# Thruster_Ctl.net
KiCad netlist of a schematic drawn in EAGLE
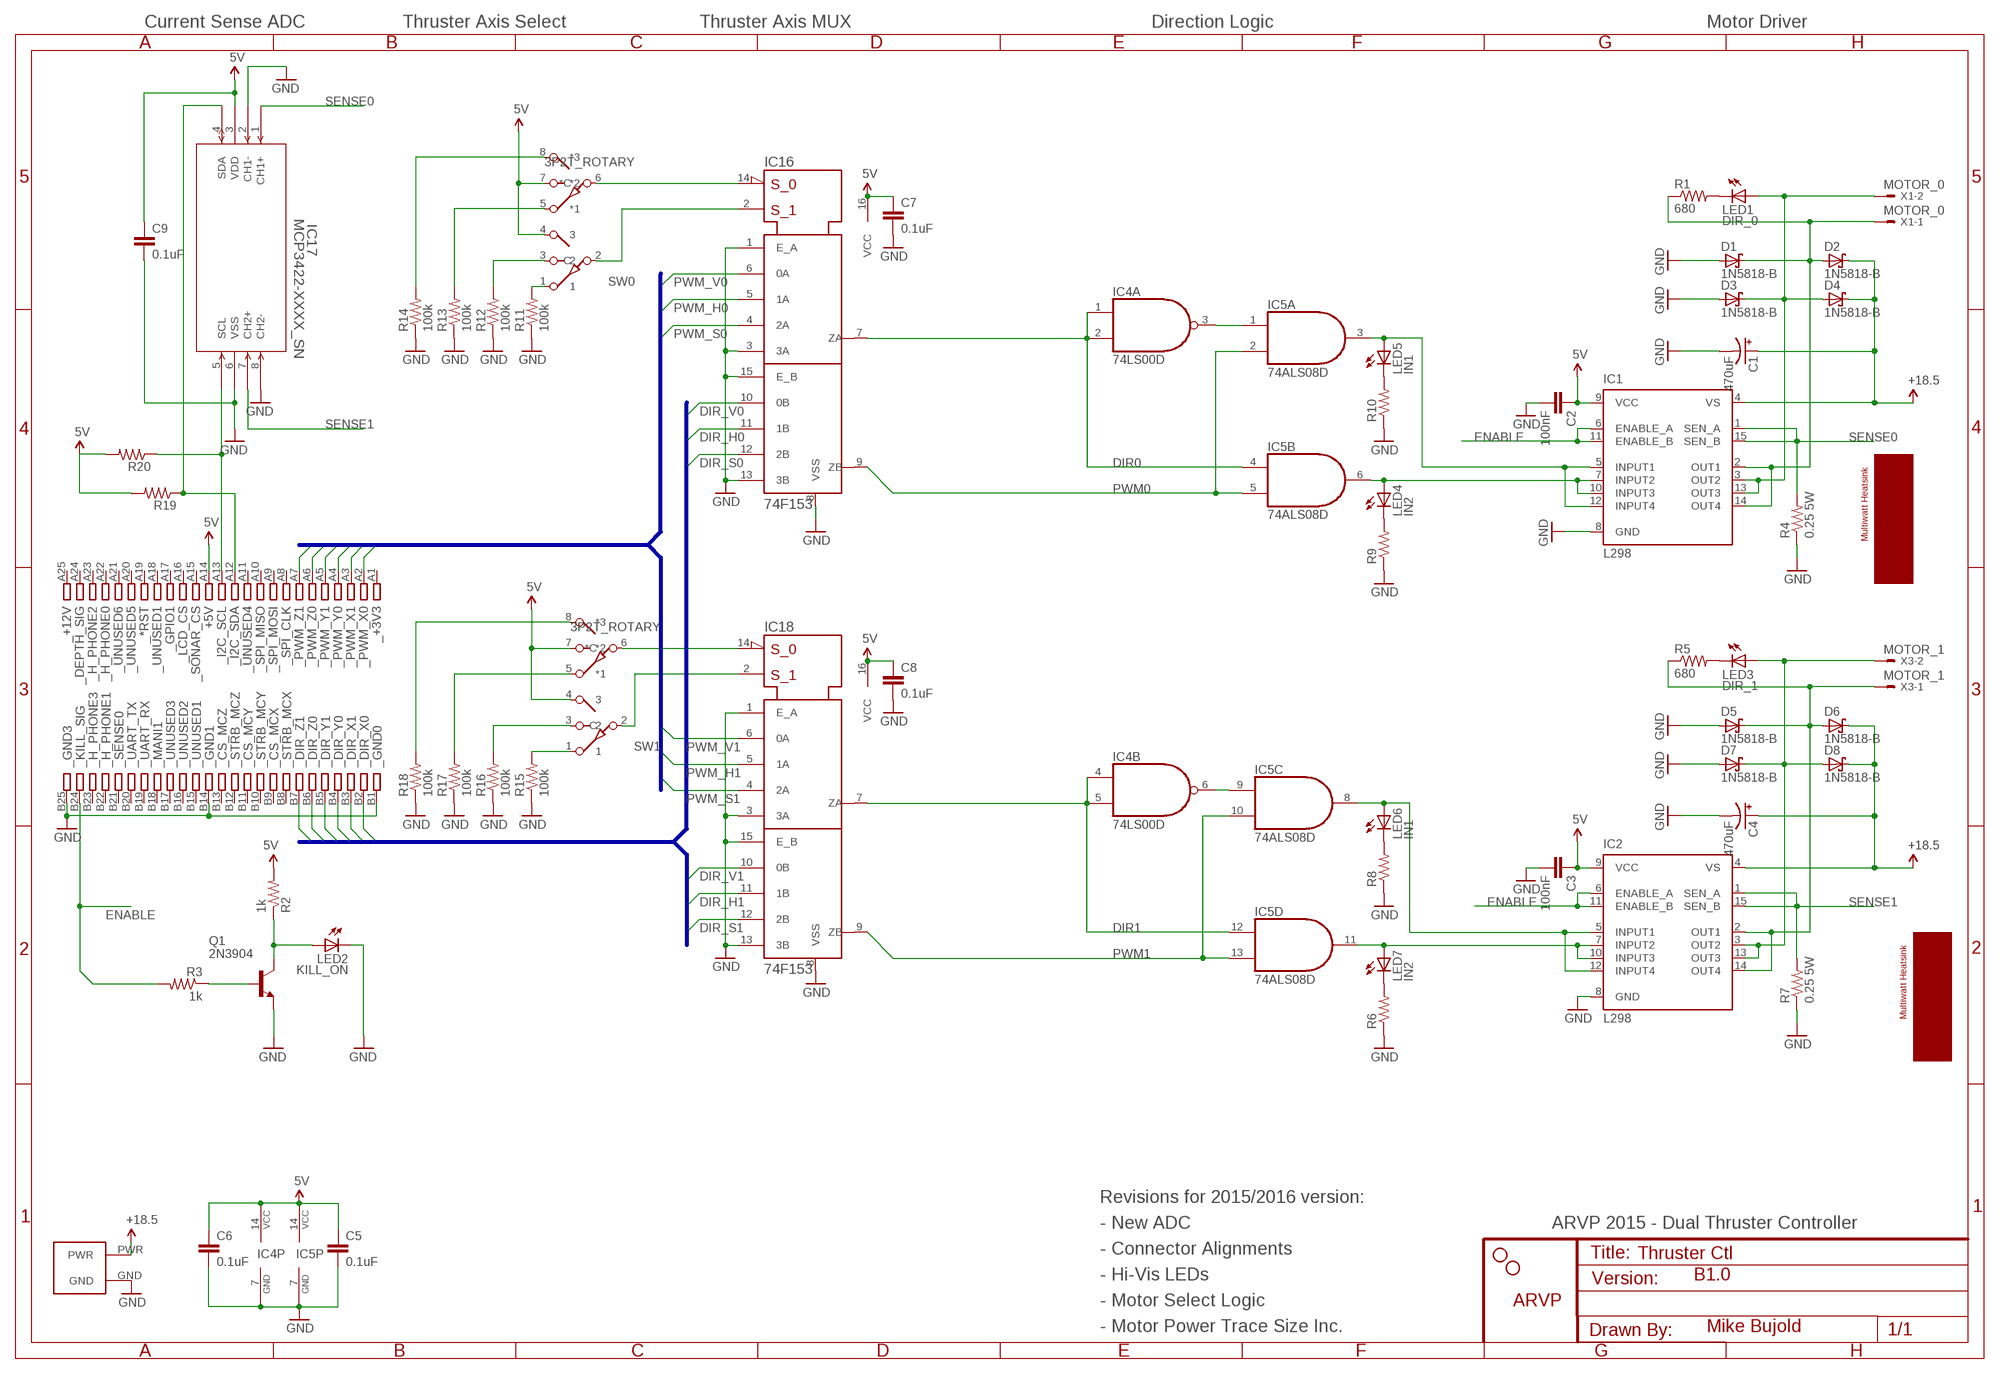
[diagram p0: schematic, sheet 1]

(export (version "E")
  (design (tool "Eeschema 10.0.6"))
  (components
    (comp (ref "C1")
      (value "470uF")
      (footprint "eagle-import:E25-10")
      (libsource (lib "eagle-import") (part "CPOL-USE25-10AXIAL"))
    )
    (comp (ref "C2")
      (value "100nF")
      (footprint "eagle-import:CAP-PTH-SMALL")
      (libsource (lib "eagle-import") (part "CAPPTH"))
    )
    (comp (ref "C3")
      (value "100nF")
      (footprint "eagle-import:CAP-PTH-SMALL")
      (libsource (lib "eagle-import") (part "CAPPTH"))
    )
    (comp (ref "C4")
      (value "470uF")
      (footprint "eagle-import:E25-10")
      (libsource (lib "eagle-import") (part "CPOL-USE25-10AXIAL"))
    )
    (comp (ref "C5")
      (value "0.1uF")
      (footprint "eagle-import:1206")
      (libsource (lib "eagle-import") (part "SparkFun-Capacitors_CAP1206"))
    )
    (comp (ref "C6")
      (value "0.1uF")
      (footprint "eagle-import:1206")
      (libsource (lib "eagle-import") (part "SparkFun-Capacitors_CAP1206"))
    )
    (comp (ref "C7")
      (value "0.1uF")
      (footprint "eagle-import:1206")
      (libsource (lib "eagle-import") (part "SparkFun-Capacitors_CAP1206"))
    )
    (comp (ref "C8")
      (value "0.1uF")
      (footprint "eagle-import:1206")
      (libsource (lib "eagle-import") (part "SparkFun-Capacitors_CAP1206"))
    )
    (comp (ref "C9")
      (value "0.1uF")
      (footprint "eagle-import:1206")
      (libsource (lib "eagle-import") (part "SparkFun-Capacitors_CAP1206"))
    )
    (comp (ref "D1")
      (value "1N5818-B")
      (footprint "eagle-import:DO41-7.6")
      (libsource (lib "eagle-import") (part "1N5818-B"))
    )
    (comp (ref "D2")
      (value "1N5818-B")
      (footprint "eagle-import:DO41-7.6")
      (libsource (lib "eagle-import") (part "1N5818-B"))
    )
    (comp (ref "D3")
      (value "1N5818-B")
      (footprint "eagle-import:DO41-7.6")
      (libsource (lib "eagle-import") (part "1N5818-B"))
    )
    (comp (ref "D4")
      (value "1N5818-B")
      (footprint "eagle-import:DO41-7.6")
      (libsource (lib "eagle-import") (part "1N5818-B"))
    )
    (comp (ref "D5")
      (value "1N5818-B")
      (footprint "eagle-import:DO41-7.6")
      (libsource (lib "eagle-import") (part "1N5818-B"))
    )
    (comp (ref "D6")
      (value "1N5818-B")
      (footprint "eagle-import:DO41-7.6")
      (libsource (lib "eagle-import") (part "1N5818-B"))
    )
    (comp (ref "D7")
      (value "1N5818-B")
      (footprint "eagle-import:DO41-7.6")
      (libsource (lib "eagle-import") (part "1N5818-B"))
    )
    (comp (ref "D8")
      (value "1N5818-B")
      (footprint "eagle-import:DO41-7.6")
      (libsource (lib "eagle-import") (part "1N5818-B"))
    )
    (comp (ref "IC1")
      (value "L298")
      (footprint "eagle-import:MULTIWATT-15")
      (fields (field (name "MPN") "L298N"))
      (libsource (lib "eagle-import") (part "L298"))
    )
    (comp (ref "IC2")
      (value "L298")
      (footprint "eagle-import:MULTIWATT-15")
      (fields (field (name "MPN") "L298N"))
      (libsource (lib "eagle-import") (part "L298"))
    )
    (comp (ref "IC4")
      (value "74LS00D")
      (footprint "eagle-import:SO14")
      (libsource (lib "eagle-import") (part "7400DLS"))
    )
    (comp (ref "IC5")
      (value "74ALS08D")
      (footprint "eagle-import:SO14")
      (libsource (lib "eagle-import") (part "7408DALS"))
    )
    (comp (ref "IC16")
      (value "74F153")
      (footprint "eagle-import:SO16")
      (libsource (lib "eagle-import") (part "74F153"))
    )
    (comp (ref "IC17")
      (value "MCP3422-XXXX_SN")
      (footprint "eagle-import:SOIC8-N_MC")
      (libsource (lib "eagle-import") (part "MCP3422-XXXX_SN"))
    )
    (comp (ref "IC18")
      (value "74F153")
      (footprint "eagle-import:SO16")
      (libsource (lib "eagle-import") (part "74F153"))
    )
    (comp (ref "JP1")
      (value "STAND-OFF")
      (footprint "eagle-import:STAND-OFF")
      (libsource (lib "eagle-import") (part "STAND-OFF"))
    )
    (comp (ref "JP4")
      (value "STAND-OFF")
      (footprint "eagle-import:STAND-OFF")
      (libsource (lib "eagle-import") (part "STAND-OFF"))
    )
    (comp (ref "LED1")
      (value "DIR_0")
      (footprint "eagle-import:LED5MM")
      (libsource (lib "eagle-import") (part "led_LED5MM"))
    )
    (comp (ref "LED2")
      (value "KILL_ON")
      (footprint "eagle-import:LED5MM")
      (libsource (lib "eagle-import") (part "led_LED5MM"))
    )
    (comp (ref "LED3")
      (value "DIR_1")
      (footprint "eagle-import:LED5MM")
      (libsource (lib "eagle-import") (part "led_LED5MM"))
    )
    (comp (ref "LED4")
      (value "IN2")
      (footprint "eagle-import:1206")
      (libsource (lib "eagle-import") (part "LEDSMT1206"))
    )
    (comp (ref "LED5")
      (value "IN1")
      (footprint "eagle-import:1206")
      (libsource (lib "eagle-import") (part "LEDSMT1206"))
    )
    (comp (ref "LED6")
      (value "IN1")
      (footprint "eagle-import:1206")
      (libsource (lib "eagle-import") (part "LEDSMT1206"))
    )
    (comp (ref "LED7")
      (value "IN2")
      (footprint "eagle-import:1206")
      (libsource (lib "eagle-import") (part "LEDSMT1206"))
    )
    (comp (ref "Q1")
      (value "2N3904")
      (footprint "eagle-import:TO92")
      (libsource (lib "eagle-import") (part "2N3904"))
    )
    (comp (ref "R1")
      (value "680")
      (footprint "eagle-import:AXIAL-0.4")
      (libsource (lib "eagle-import") (part "RESISTORPTH-1/4W"))
    )
    (comp (ref "R2")
      (value "1k")
      (footprint "eagle-import:AXIAL-0.4")
      (libsource (lib "eagle-import") (part "RESISTORPTH-1/4W"))
    )
    (comp (ref "R3")
      (value "1k")
      (footprint "eagle-import:AXIAL-0.4")
      (libsource (lib "eagle-import") (part "RESISTORPTH-1/4W"))
    )
    (comp (ref "R4")
      (value "0.25 5W")
      (footprint "eagle-import:0922_22")
      (libsource (lib "eagle-import") (part "RESISTOR"))
    )
    (comp (ref "R5")
      (value "680")
      (footprint "eagle-import:AXIAL-0.4")
      (libsource (lib "eagle-import") (part "RESISTORPTH-1/4W"))
    )
    (comp (ref "R6")
      (value "RESISTOR1206")
      (footprint "eagle-import:1206")
      (libsource (lib "eagle-import") (part "SparkFun-Passives_RESISTOR1206"))
    )
    (comp (ref "R7")
      (value "0.25 5W")
      (footprint "eagle-import:0922_22")
      (libsource (lib "eagle-import") (part "RESISTOR"))
    )
    (comp (ref "R8")
      (value "RESISTOR1206")
      (footprint "eagle-import:1206")
      (libsource (lib "eagle-import") (part "SparkFun-Passives_RESISTOR1206"))
    )
    (comp (ref "R9")
      (value "RESISTOR1206")
      (footprint "eagle-import:1206")
      (libsource (lib "eagle-import") (part "SparkFun-Passives_RESISTOR1206"))
    )
    (comp (ref "R10")
      (value "RESISTOR1206")
      (footprint "eagle-import:1206")
      (libsource (lib "eagle-import") (part "SparkFun-Passives_RESISTOR1206"))
    )
    (comp (ref "R11")
      (value "100k")
      (footprint "eagle-import:1206")
      (libsource (lib "eagle-import") (part "SparkFun-Passives_RESISTOR1206"))
    )
    (comp (ref "R12")
      (value "100k")
      (footprint "eagle-import:1206")
      (libsource (lib "eagle-import") (part "SparkFun-Passives_RESISTOR1206"))
    )
    (comp (ref "R13")
      (value "100k")
      (footprint "eagle-import:1206")
      (libsource (lib "eagle-import") (part "SparkFun-Passives_RESISTOR1206"))
    )
    (comp (ref "R14")
      (value "100k")
      (footprint "eagle-import:1206")
      (libsource (lib "eagle-import") (part "SparkFun-Passives_RESISTOR1206"))
    )
    (comp (ref "R15")
      (value "100k")
      (footprint "eagle-import:1206")
      (libsource (lib "eagle-import") (part "SparkFun-Passives_RESISTOR1206"))
    )
    (comp (ref "R16")
      (value "100k")
      (footprint "eagle-import:1206")
      (libsource (lib "eagle-import") (part "SparkFun-Passives_RESISTOR1206"))
    )
    (comp (ref "R17")
      (value "100k")
      (footprint "eagle-import:1206")
      (libsource (lib "eagle-import") (part "SparkFun-Passives_RESISTOR1206"))
    )
    (comp (ref "R18")
      (value "100k")
      (footprint "eagle-import:1206")
      (libsource (lib "eagle-import") (part "SparkFun-Passives_RESISTOR1206"))
    )
    (comp (ref "R19")
      (value "RESISTOR1206")
      (footprint "eagle-import:1206")
      (libsource (lib "eagle-import") (part "SparkFun-Passives_RESISTOR1206"))
    )
    (comp (ref "R20")
      (value "RESISTOR1206")
      (footprint "eagle-import:1206")
      (libsource (lib "eagle-import") (part "SparkFun-Passives_RESISTOR1206"))
    )
    (comp (ref "SW0")
      (value "3P2T_ROTARY")
      (footprint "eagle-import:DIL08")
      (libsource (lib "eagle-import") (part "3P2T_ROTARY"))
    )
    (comp (ref "SW1")
      (value "3P2T_ROTARY")
      (footprint "eagle-import:DIL08")
      (libsource (lib "eagle-import") (part "3P2T_ROTARY"))
    )
    (comp (ref "U$4")
      (value "ARVP_LOGO")
      (footprint "eagle-import:ARVP")
      (libsource (lib "eagle-import") (part "ARVP_LOGO"))
    )
    (comp (ref "U$7")
      (value "AND_PWR")
      (footprint "eagle-import:AND_PWR")
      (libsource (lib "eagle-import") (part "AND_PWR"))
    )
    (comp (ref "U$9")
      (value "L298_HS")
      (footprint "eagle-import:HEATSINK_MW")
      (libsource (lib "eagle-import") (part "L298_HS"))
    )
    (comp (ref "U$10")
      (value "L298_HS")
      (footprint "eagle-import:HEATSINK_MW")
      (libsource (lib "eagle-import") (part "L298_HS"))
    )
    (comp (ref "U$19")
      (value "CARD_50PIN")
      (footprint "eagle-import:CARD_50PIN")
      (libsource (lib "eagle-import") (part "CARD_50PIN"))
    )
    (comp (ref "X1")
      (value "MOTOR_0")
      (footprint "eagle-import:KK-156-2")
      (libsource (lib "eagle-import") (part "KK-156-2"))
    )
    (comp (ref "X3")
      (value "MOTOR_1")
      (footprint "eagle-import:KK-156-2")
      (libsource (lib "eagle-import") (part "KK-156-2"))
    )
  )
  (nets
    (net (code "1") (name "+18.5") (class "Default")
      (node (ref "C1") (pin "+") (pinfunction "+_+") (pintype "passive"))
      (node (ref "C4") (pin "+") (pinfunction "+_+") (pintype "passive"))
      (node (ref "D2") (pin "C") (pinfunction "C_C") (pintype "passive"))
      (node (ref "D4") (pin "C") (pinfunction "C_C") (pintype "passive"))
      (node (ref "D6") (pin "C") (pinfunction "C_C") (pintype "passive"))
      (node (ref "D8") (pin "C") (pinfunction "C_C") (pintype "passive"))
      (node (ref "IC1") (pin "4") (pinfunction "VS_4") (pintype "power_in"))
      (node (ref "IC2") (pin "4") (pinfunction "VS_4") (pintype "power_in"))
      (node (ref "U$7") (pin "PWR") (pinfunction "PWR_PWR") (pintype "bidirectional"))
    )
    (net (code "2") (name "/DIR0") (class "Default")
      (node (ref "IC16") (pin "7") (pinfunction "ZA_7") (pintype "output"))
      (node (ref "IC4") (pin "1") (pinfunction "I0_1") (pintype "input"))
      (node (ref "IC4") (pin "2") (pinfunction "I1_2") (pintype "input"))
      (node (ref "IC5") (pin "4") (pinfunction "I0_4") (pintype "input"))
    )
    (net (code "3") (name "/DIR1") (class "Default")
      (node (ref "IC18") (pin "7") (pinfunction "ZA_7") (pintype "output"))
      (node (ref "IC4") (pin "4") (pinfunction "I0_4") (pintype "input"))
      (node (ref "IC4") (pin "5") (pinfunction "I1_5") (pintype "input"))
      (node (ref "IC5") (pin "12") (pinfunction "I0_12") (pintype "input"))
    )
    (net (code "4") (name "/DIR_H0") (class "Default")
      (node (ref "IC16") (pin "11") (pinfunction "1B_11") (pintype "input"))
      (node (ref "U$19") (pin "B4") (pinfunction "B4_B4") (pintype "bidirectional"))
    )
    (net (code "5") (name "/DIR_H1") (class "Default")
      (node (ref "IC18") (pin "11") (pinfunction "1B_11") (pintype "input"))
      (node (ref "U$19") (pin "B5") (pinfunction "B5_B5") (pintype "bidirectional"))
    )
    (net (code "6") (name "/DIR_S0") (class "Default")
      (node (ref "IC16") (pin "12") (pinfunction "2B_12") (pintype "input"))
      (node (ref "U$19") (pin "B6") (pinfunction "B6_B6") (pintype "bidirectional"))
    )
    (net (code "7") (name "/DIR_S1") (class "Default")
      (node (ref "IC18") (pin "12") (pinfunction "2B_12") (pintype "input"))
      (node (ref "U$19") (pin "B7") (pinfunction "B7_B7") (pintype "bidirectional"))
    )
    (net (code "8") (name "/DIR_V0") (class "Default")
      (node (ref "IC16") (pin "10") (pinfunction "0B_10") (pintype "input"))
      (node (ref "U$19") (pin "B2") (pinfunction "B2_B2") (pintype "bidirectional"))
    )
    (net (code "9") (name "/DIR_V1") (class "Default")
      (node (ref "IC18") (pin "10") (pinfunction "0B_10") (pintype "input"))
      (node (ref "U$19") (pin "B3") (pinfunction "B3_B3") (pintype "bidirectional"))
    )
    (net (code "10") (name "/ENABLE") (class "Default")
      (node (ref "IC1") (pin "11") (pinfunction "ENABLE_B_11") (pintype "input"))
      (node (ref "IC1") (pin "6") (pinfunction "ENABLE_A_6") (pintype "input"))
      (node (ref "IC2") (pin "11") (pinfunction "ENABLE_B_11") (pintype "input"))
      (node (ref "IC2") (pin "6") (pinfunction "ENABLE_A_6") (pintype "input"))
      (node (ref "R3") (pin "P$2") (pinfunction "2_P$2") (pintype "passive"))
      (node (ref "U$19") (pin "B24") (pinfunction "B24_B24") (pintype "bidirectional"))
    )
    (net (code "11") (name "/PWM0") (class "Default")
      (node (ref "IC16") (pin "9") (pinfunction "ZB_9") (pintype "output"))
      (node (ref "IC5") (pin "2") (pinfunction "I1_2") (pintype "input"))
      (node (ref "IC5") (pin "5") (pinfunction "I1_5") (pintype "input"))
    )
    (net (code "12") (name "/PWM1") (class "Default")
      (node (ref "IC18") (pin "9") (pinfunction "ZB_9") (pintype "output"))
      (node (ref "IC5") (pin "10") (pinfunction "I1_10") (pintype "input"))
      (node (ref "IC5") (pin "13") (pinfunction "I1_13") (pintype "input"))
    )
    (net (code "13") (name "/PWM_H0") (class "Default")
      (node (ref "IC16") (pin "5") (pinfunction "1A_5") (pintype "input"))
      (node (ref "U$19") (pin "A4") (pinfunction "A4_A4") (pintype "bidirectional"))
    )
    (net (code "14") (name "/PWM_H1") (class "Default")
      (node (ref "IC18") (pin "5") (pinfunction "1A_5") (pintype "input"))
      (node (ref "U$19") (pin "A5") (pinfunction "A5_A5") (pintype "bidirectional"))
    )
    (net (code "15") (name "/PWM_S0") (class "Default")
      (node (ref "IC16") (pin "4") (pinfunction "2A_4") (pintype "input"))
      (node (ref "U$19") (pin "A6") (pinfunction "A6_A6") (pintype "bidirectional"))
    )
    (net (code "16") (name "/PWM_S1") (class "Default")
      (node (ref "IC18") (pin "4") (pinfunction "2A_4") (pintype "input"))
      (node (ref "U$19") (pin "A7") (pinfunction "A7_A7") (pintype "bidirectional"))
    )
    (net (code "17") (name "/PWM_V0") (class "Default")
      (node (ref "IC16") (pin "6") (pinfunction "0A_6") (pintype "input"))
      (node (ref "U$19") (pin "A2") (pinfunction "A2_A2") (pintype "bidirectional"))
    )
    (net (code "18") (name "/PWM_V1") (class "Default")
      (node (ref "IC18") (pin "6") (pinfunction "0A_6") (pintype "input"))
      (node (ref "U$19") (pin "A3") (pinfunction "A3_A3") (pintype "bidirectional"))
    )
    (net (code "19") (name "/SENSE0") (class "Default")
      (node (ref "IC1") (pin "1") (pinfunction "SEN_A_1") (pintype "input"))
      (node (ref "IC1") (pin "15") (pinfunction "SEN_B_15") (pintype "input"))
      (node (ref "IC17") (pin "1") (pinfunction "CH1+_1") (pintype "input"))
      (node (ref "R4") (pin "2") (pinfunction "2_2") (pintype "passive"))
    )
    (net (code "20") (name "/SENSE1") (class "Default")
      (node (ref "IC17") (pin "7") (pinfunction "CH2+_7") (pintype "input"))
      (node (ref "IC2") (pin "1") (pinfunction "SEN_A_1") (pintype "input"))
      (node (ref "IC2") (pin "15") (pinfunction "SEN_B_15") (pintype "input"))
      (node (ref "R7") (pin "2") (pinfunction "2_2") (pintype "passive"))
    )
    (net (code "21") (name "5V") (class "Default")
      (node (ref "C2") (pin "1") (pinfunction "1_1") (pintype "passive"))
      (node (ref "C3") (pin "1") (pinfunction "1_1") (pintype "passive"))
      (node (ref "C5") (pin "1") (pinfunction "1_1") (pintype "passive"))
      (node (ref "C6") (pin "1") (pinfunction "1_1") (pintype "passive"))
      (node (ref "C7") (pin "1") (pinfunction "1_1") (pintype "passive"))
      (node (ref "C8") (pin "1") (pinfunction "1_1") (pintype "passive"))
      (node (ref "C9") (pin "1") (pinfunction "1_1") (pintype "passive"))
      (node (ref "IC1") (pin "9") (pinfunction "VCC_9") (pintype "power_in"))
      (node (ref "IC16") (pin "16") (pinfunction "VCC_16") (pintype "power_in"))
      (node (ref "IC17") (pin "3") (pinfunction "VDD_3") (pintype "power_in"))
      (node (ref "IC18") (pin "16") (pinfunction "VCC_16") (pintype "power_in"))
      (node (ref "IC2") (pin "9") (pinfunction "VCC_9") (pintype "power_in"))
      (node (ref "IC4") (pin "14") (pinfunction "VCC_14") (pintype "power_in"))
      (node (ref "IC5") (pin "14") (pinfunction "VCC_14") (pintype "power_in"))
      (node (ref "R19") (pin "2") (pinfunction "2_2") (pintype "passive"))
      (node (ref "R2") (pin "P$2") (pinfunction "2_P$2") (pintype "passive"))
      (node (ref "R20") (pin "2") (pinfunction "2_2") (pintype "passive"))
      (node (ref "SW0") (pin "4") (pinfunction "3_4") (pintype "passive"))
      (node (ref "SW0") (pin "7") (pinfunction "*2_7") (pintype "passive"))
      (node (ref "SW1") (pin "4") (pinfunction "3_4") (pintype "passive"))
      (node (ref "SW1") (pin "7") (pinfunction "*2_7") (pintype "passive"))
      (node (ref "U$19") (pin "A14") (pinfunction "A14_A14") (pintype "bidirectional"))
    )
    (net (code "22") (name "GND") (class "Default")
      (node (ref "C1") (pin "-") (pinfunction "-_-") (pintype "passive"))
      (node (ref "C2") (pin "2") (pinfunction "2_2") (pintype "passive"))
      (node (ref "C3") (pin "2") (pinfunction "2_2") (pintype "passive"))
      (node (ref "C4") (pin "-") (pinfunction "-_-") (pintype "passive"))
      (node (ref "C5") (pin "2") (pinfunction "2_2") (pintype "passive"))
      (node (ref "C6") (pin "2") (pinfunction "2_2") (pintype "passive"))
      (node (ref "C7") (pin "2") (pinfunction "2_2") (pintype "passive"))
      (node (ref "C8") (pin "2") (pinfunction "2_2") (pintype "passive"))
      (node (ref "C9") (pin "2") (pinfunction "2_2") (pintype "passive"))
      (node (ref "D1") (pin "A") (pinfunction "A_A") (pintype "passive"))
      (node (ref "D3") (pin "A") (pinfunction "A_A") (pintype "passive"))
      (node (ref "D5") (pin "A") (pinfunction "A_A") (pintype "passive"))
      (node (ref "D7") (pin "A") (pinfunction "A_A") (pintype "passive"))
      (node (ref "IC1") (pin "8") (pinfunction "GND_8") (pintype "power_in"))
      (node (ref "IC16") (pin "1") (pinfunction "E_A_1") (pintype "input"))
      (node (ref "IC16") (pin "13") (pinfunction "3B_13") (pintype "input"))
      (node (ref "IC16") (pin "15") (pinfunction "E_B_15") (pintype "input"))
      (node (ref "IC16") (pin "3") (pinfunction "3A_3") (pintype "input"))
      (node (ref "IC16") (pin "8") (pinfunction "VSS_8") (pintype "power_in"))
      (node (ref "IC17") (pin "2") (pinfunction "CH1-_2") (pintype "input"))
      (node (ref "IC17") (pin "6") (pinfunction "VSS_6") (pintype "power_in"))
      (node (ref "IC17") (pin "8") (pinfunction "CH2-_8") (pintype "input"))
      (node (ref "IC18") (pin "1") (pinfunction "E_A_1") (pintype "input"))
      (node (ref "IC18") (pin "13") (pinfunction "3B_13") (pintype "input"))
      (node (ref "IC18") (pin "15") (pinfunction "E_B_15") (pintype "input"))
      (node (ref "IC18") (pin "3") (pinfunction "3A_3") (pintype "input"))
      (node (ref "IC18") (pin "8") (pinfunction "VSS_8") (pintype "power_in"))
      (node (ref "IC2") (pin "8") (pinfunction "GND_8") (pintype "power_in"))
      (node (ref "IC4") (pin "7") (pinfunction "GND_7") (pintype "power_in"))
      (node (ref "IC5") (pin "7") (pinfunction "GND_7") (pintype "power_in"))
      (node (ref "LED2") (pin "K") (pinfunction "C_K") (pintype "passive"))
      (node (ref "Q1") (pin "3") (pinfunction "E_3") (pintype "passive"))
      (node (ref "R10") (pin "1") (pinfunction "1_1") (pintype "passive"))
      (node (ref "R11") (pin "1") (pinfunction "1_1") (pintype "passive"))
      (node (ref "R12") (pin "1") (pinfunction "1_1") (pintype "passive"))
      (node (ref "R13") (pin "1") (pinfunction "1_1") (pintype "passive"))
      (node (ref "R14") (pin "1") (pinfunction "1_1") (pintype "passive"))
      (node (ref "R15") (pin "1") (pinfunction "1_1") (pintype "passive"))
      (node (ref "R16") (pin "1") (pinfunction "1_1") (pintype "passive"))
      (node (ref "R17") (pin "1") (pinfunction "1_1") (pintype "passive"))
      (node (ref "R18") (pin "1") (pinfunction "1_1") (pintype "passive"))
      (node (ref "R4") (pin "1") (pinfunction "1_1") (pintype "passive"))
      (node (ref "R6") (pin "1") (pinfunction "1_1") (pintype "passive"))
      (node (ref "R7") (pin "1") (pinfunction "1_1") (pintype "passive"))
      (node (ref "R8") (pin "1") (pinfunction "1_1") (pintype "passive"))
      (node (ref "R9") (pin "1") (pinfunction "1_1") (pintype "passive"))
      (node (ref "U$19") (pin "B1") (pinfunction "B1_B1") (pintype "bidirectional"))
      (node (ref "U$19") (pin "B14") (pinfunction "B14_B14") (pintype "bidirectional"))
      (node (ref "U$19") (pin "B25") (pinfunction "B25_B25") (pintype "bidirectional"))
      (node (ref "U$7") (pin "GND") (pinfunction "GND_GND") (pintype "bidirectional"))
    )
    (net (code "23") (name "Net-(IC1-INPUT1)") (class "Default")
      (node (ref "IC1") (pin "12") (pinfunction "INPUT4_12") (pintype "input"))
      (node (ref "IC1") (pin "5") (pinfunction "INPUT1_5") (pintype "input"))
      (node (ref "IC5") (pin "3") (pinfunction "O_3") (pintype "output"))
      (node (ref "LED5") (pin "A") (pinfunction "A_A") (pintype "passive"))
    )
    (net (code "24") (name "Net-(IC1-INPUT2)") (class "Default")
      (node (ref "IC1") (pin "10") (pinfunction "INPUT3_10") (pintype "input"))
      (node (ref "IC1") (pin "7") (pinfunction "INPUT2_7") (pintype "input"))
      (node (ref "IC5") (pin "6") (pinfunction "O_6") (pintype "output"))
      (node (ref "LED4") (pin "A") (pinfunction "A_A") (pintype "passive"))
    )
    (net (code "25") (name "Net-(IC1-OUT1)") (class "Default")
      (node (ref "D1") (pin "C") (pinfunction "C_C") (pintype "passive"))
      (node (ref "D2") (pin "A") (pinfunction "A_A") (pintype "passive"))
      (node (ref "IC1") (pin "14") (pinfunction "OUT4_14") (pintype "output"))
      (node (ref "IC1") (pin "2") (pinfunction "OUT1_2") (pintype "output"))
      (node (ref "R1") (pin "P$1") (pinfunction "1_P$1") (pintype "passive"))
      (node (ref "X1") (pin "1") (pinfunction "S_1") (pintype "passive"))
    )
    (net (code "26") (name "Net-(IC1-OUT2)") (class "Default")
      (node (ref "D3") (pin "C") (pinfunction "C_C") (pintype "passive"))
      (node (ref "D4") (pin "A") (pinfunction "A_A") (pintype "passive"))
      (node (ref "IC1") (pin "13") (pinfunction "OUT3_13") (pintype "output"))
      (node (ref "IC1") (pin "3") (pinfunction "OUT2_3") (pintype "output"))
      (node (ref "LED1") (pin "A") (pinfunction "A_A") (pintype "passive"))
      (node (ref "X1") (pin "2") (pinfunction "S_2") (pintype "passive"))
    )
    (net (code "27") (name "Net-(IC2-INPUT1)") (class "Default")
      (node (ref "IC2") (pin "12") (pinfunction "INPUT4_12") (pintype "input"))
      (node (ref "IC2") (pin "5") (pinfunction "INPUT1_5") (pintype "input"))
      (node (ref "IC5") (pin "8") (pinfunction "O_8") (pintype "output"))
      (node (ref "LED6") (pin "A") (pinfunction "A_A") (pintype "passive"))
    )
    (net (code "28") (name "Net-(IC2-INPUT2)") (class "Default")
      (node (ref "IC2") (pin "10") (pinfunction "INPUT3_10") (pintype "input"))
      (node (ref "IC2") (pin "7") (pinfunction "INPUT2_7") (pintype "input"))
      (node (ref "IC5") (pin "11") (pinfunction "O_11") (pintype "output"))
      (node (ref "LED7") (pin "A") (pinfunction "A_A") (pintype "passive"))
    )
    (net (code "29") (name "Net-(IC2-OUT1)") (class "Default")
      (node (ref "D5") (pin "C") (pinfunction "C_C") (pintype "passive"))
      (node (ref "D6") (pin "A") (pinfunction "A_A") (pintype "passive"))
      (node (ref "IC2") (pin "14") (pinfunction "OUT4_14") (pintype "output"))
      (node (ref "IC2") (pin "2") (pinfunction "OUT1_2") (pintype "output"))
      (node (ref "R5") (pin "P$1") (pinfunction "1_P$1") (pintype "passive"))
      (node (ref "X3") (pin "1") (pinfunction "S_1") (pintype "passive"))
    )
    (net (code "30") (name "Net-(IC2-OUT2)") (class "Default")
      (node (ref "D7") (pin "C") (pinfunction "C_C") (pintype "passive"))
      (node (ref "D8") (pin "A") (pinfunction "A_A") (pintype "passive"))
      (node (ref "IC2") (pin "13") (pinfunction "OUT3_13") (pintype "output"))
      (node (ref "IC2") (pin "3") (pinfunction "OUT2_3") (pintype "output"))
      (node (ref "LED3") (pin "A") (pinfunction "A_A") (pintype "passive"))
      (node (ref "X3") (pin "2") (pinfunction "S_2") (pintype "passive"))
    )
    (net (code "31") (name "Net-(IC4A-O)") (class "Default")
      (node (ref "IC4") (pin "3") (pinfunction "O_3") (pintype "output"))
      (node (ref "IC5") (pin "1") (pinfunction "I0_1") (pintype "input"))
    )
    (net (code "32") (name "Net-(IC4B-O)") (class "Default")
      (node (ref "IC4") (pin "6") (pinfunction "O_6") (pintype "output"))
      (node (ref "IC5") (pin "9") (pinfunction "I0_9") (pintype "input"))
    )
    (net (code "33") (name "Net-(IC16-S0)") (class "Default")
      (node (ref "IC16") (pin "14") (pinfunction "S0_14") (pintype "input"))
      (node (ref "SW0") (pin "6") (pinfunction "*C_6") (pintype "passive"))
    )
    (net (code "34") (name "Net-(IC16-S1)") (class "Default")
      (node (ref "IC16") (pin "2") (pinfunction "S1_2") (pintype "input"))
      (node (ref "SW0") (pin "2") (pinfunction "C_2") (pintype "passive"))
    )
    (net (code "35") (name "Net-(IC17-SCL)") (class "Default")
      (node (ref "IC17") (pin "5") (pinfunction "SCL_5") (pintype "input"))
      (node (ref "R20") (pin "1") (pinfunction "1_1") (pintype "passive"))
      (node (ref "U$19") (pin "A13") (pinfunction "A13_A13") (pintype "bidirectional"))
    )
    (net (code "36") (name "Net-(IC17-SDA)") (class "Default")
      (node (ref "IC17") (pin "4") (pinfunction "SDA_4") (pintype "bidirectional"))
      (node (ref "R19") (pin "1") (pinfunction "1_1") (pintype "passive"))
      (node (ref "U$19") (pin "A12") (pinfunction "A12_A12") (pintype "bidirectional"))
    )
    (net (code "37") (name "Net-(IC18-S0)") (class "Default")
      (node (ref "IC18") (pin "14") (pinfunction "S0_14") (pintype "input"))
      (node (ref "SW1") (pin "6") (pinfunction "*C_6") (pintype "passive"))
    )
    (net (code "38") (name "Net-(IC18-S1)") (class "Default")
      (node (ref "IC18") (pin "2") (pinfunction "S1_2") (pintype "input"))
      (node (ref "SW1") (pin "2") (pinfunction "C_2") (pintype "passive"))
    )
    (net (code "39") (name "Net-(LED1-C)") (class "Default")
      (node (ref "LED1") (pin "K") (pinfunction "C_K") (pintype "passive"))
      (node (ref "R1") (pin "P$2") (pinfunction "2_P$2") (pintype "passive"))
    )
    (net (code "40") (name "Net-(LED3-C)") (class "Default")
      (node (ref "LED3") (pin "K") (pinfunction "C_K") (pintype "passive"))
      (node (ref "R5") (pin "P$2") (pinfunction "2_P$2") (pintype "passive"))
    )
    (net (code "41") (name "Net-(LED4-PadC)") (class "Default")
      (node (ref "LED4") (pin "C") (pinfunction "C_C") (pintype "passive"))
      (node (ref "R9") (pin "2") (pinfunction "2_2") (pintype "passive"))
    )
    (net (code "42") (name "Net-(LED5-PadC)") (class "Default")
      (node (ref "LED5") (pin "C") (pinfunction "C_C") (pintype "passive"))
      (node (ref "R10") (pin "2") (pinfunction "2_2") (pintype "passive"))
    )
    (net (code "43") (name "Net-(LED6-PadC)") (class "Default")
      (node (ref "LED6") (pin "C") (pinfunction "C_C") (pintype "passive"))
      (node (ref "R8") (pin "2") (pinfunction "2_2") (pintype "passive"))
    )
    (net (code "44") (name "Net-(LED7-PadC)") (class "Default")
      (node (ref "LED7") (pin "C") (pinfunction "C_C") (pintype "passive"))
      (node (ref "R6") (pin "2") (pinfunction "2_2") (pintype "passive"))
    )
    (net (code "45") (name "Net-(Q1-B)") (class "Default")
      (node (ref "Q1") (pin "2") (pinfunction "B_2") (pintype "passive"))
      (node (ref "R3") (pin "P$1") (pinfunction "1_P$1") (pintype "passive"))
    )
    (net (code "46") (name "Net-(Q1-C)") (class "Default")
      (node (ref "LED2") (pin "A") (pinfunction "A_A") (pintype "passive"))
      (node (ref "Q1") (pin "1") (pinfunction "C_1") (pintype "passive"))
      (node (ref "R2") (pin "P$1") (pinfunction "1_P$1") (pintype "passive"))
    )
    (net (code "47") (name "Net-(R11-Pad2)") (class "Default")
      (node (ref "R11") (pin "2") (pinfunction "2_2") (pintype "passive"))
      (node (ref "SW0") (pin "1") (pinfunction "1_1") (pintype "passive"))
    )
    (net (code "48") (name "Net-(R15-Pad2)") (class "Default")
      (node (ref "R15") (pin "2") (pinfunction "2_2") (pintype "passive"))
      (node (ref "SW1") (pin "1") (pinfunction "1_1") (pintype "passive"))
    )
    (net (code "49") (name "Net-(SW0-*1)") (class "Default")
      (node (ref "R13") (pin "2") (pinfunction "2_2") (pintype "passive"))
      (node (ref "SW0") (pin "5") (pinfunction "*1_5") (pintype "passive"))
    )
    (net (code "50") (name "Net-(SW0-*3)") (class "Default")
      (node (ref "R14") (pin "2") (pinfunction "2_2") (pintype "passive"))
      (node (ref "SW0") (pin "8") (pinfunction "*3_8") (pintype "passive"))
    )
    (net (code "51") (name "Net-(SW0-2)") (class "Default")
      (node (ref "R12") (pin "2") (pinfunction "2_2") (pintype "passive"))
      (node (ref "SW0") (pin "3") (pinfunction "2_3") (pintype "passive"))
    )
    (net (code "52") (name "Net-(SW1-*1)") (class "Default")
      (node (ref "R17") (pin "2") (pinfunction "2_2") (pintype "passive"))
      (node (ref "SW1") (pin "5") (pinfunction "*1_5") (pintype "passive"))
    )
    (net (code "53") (name "Net-(SW1-*3)") (class "Default")
      (node (ref "R18") (pin "2") (pinfunction "2_2") (pintype "passive"))
      (node (ref "SW1") (pin "8") (pinfunction "*3_8") (pintype "passive"))
    )
    (net (code "54") (name "Net-(SW1-2)") (class "Default")
      (node (ref "R16") (pin "2") (pinfunction "2_2") (pintype "passive"))
      (node (ref "SW1") (pin "3") (pinfunction "2_3") (pintype "passive"))
    )
    (net (code "55") (name "unconnected-(U$19-PadA1)") (class "Default")
      (node (ref "U$19") (pin "A1") (pinfunction "A1_A1") (pintype "bidirectional"))
    )
    (net (code "56") (name "unconnected-(U$19-PadA8)") (class "Default")
      (node (ref "U$19") (pin "A8") (pinfunction "A8_A8") (pintype "bidirectional"))
    )
    (net (code "57") (name "unconnected-(U$19-PadA9)") (class "Default")
      (node (ref "U$19") (pin "A9") (pinfunction "A9_A9") (pintype "bidirectional"))
    )
    (net (code "58") (name "unconnected-(U$19-PadA10)") (class "Default")
      (node (ref "U$19") (pin "A10") (pinfunction "A10_A10") (pintype "bidirectional"))
    )
    (net (code "59") (name "unconnected-(U$19-PadA11)") (class "Default")
      (node (ref "U$19") (pin "A11") (pinfunction "A11_A11") (pintype "bidirectional"))
    )
    (net (code "60") (name "unconnected-(U$19-PadA15)") (class "Default")
      (node (ref "U$19") (pin "A15") (pinfunction "A15_A15") (pintype "bidirectional"))
    )
    (net (code "61") (name "unconnected-(U$19-PadA16)") (class "Default")
      (node (ref "U$19") (pin "A16") (pinfunction "A16_A16") (pintype "bidirectional"))
    )
    (net (code "62") (name "unconnected-(U$19-PadA17)") (class "Default")
      (node (ref "U$19") (pin "A17") (pinfunction "A17_A17") (pintype "bidirectional"))
    )
    (net (code "63") (name "unconnected-(U$19-PadA18)") (class "Default")
      (node (ref "U$19") (pin "A18") (pinfunction "A18_A18") (pintype "bidirectional"))
    )
    (net (code "64") (name "unconnected-(U$19-PadA19)") (class "Default")
      (node (ref "U$19") (pin "A19") (pinfunction "A19_A19") (pintype "bidirectional"))
    )
    (net (code "65") (name "unconnected-(U$19-PadA20)") (class "Default")
      (node (ref "U$19") (pin "A20") (pinfunction "A20_A20") (pintype "bidirectional"))
    )
    (net (code "66") (name "unconnected-(U$19-PadA21)") (class "Default")
      (node (ref "U$19") (pin "A21") (pinfunction "A21_A21") (pintype "bidirectional"))
    )
    (net (code "67") (name "unconnected-(U$19-PadA22)") (class "Default")
      (node (ref "U$19") (pin "A22") (pinfunction "A22_A22") (pintype "bidirectional"))
    )
    (net (code "68") (name "unconnected-(U$19-PadA23)") (class "Default")
      (node (ref "U$19") (pin "A23") (pinfunction "A23_A23") (pintype "bidirectional"))
    )
    (net (code "69") (name "unconnected-(U$19-PadA24)") (class "Default")
      (node (ref "U$19") (pin "A24") (pinfunction "A24_A24") (pintype "bidirectional"))
    )
    (net (code "70") (name "unconnected-(U$19-PadA25)") (class "Default")
      (node (ref "U$19") (pin "A25") (pinfunction "A25_A25") (pintype "bidirectional"))
    )
    (net (code "71") (name "unconnected-(U$19-PadB8)") (class "Default")
      (node (ref "U$19") (pin "B8") (pinfunction "B8_B8") (pintype "bidirectional"))
    )
    (net (code "72") (name "unconnected-(U$19-PadB9)") (class "Default")
      (node (ref "U$19") (pin "B9") (pinfunction "B9_B9") (pintype "bidirectional"))
    )
    (net (code "73") (name "unconnected-(U$19-PadB10)") (class "Default")
      (node (ref "U$19") (pin "B10") (pinfunction "B10_B10") (pintype "bidirectional"))
    )
    (net (code "74") (name "unconnected-(U$19-PadB11)") (class "Default")
      (node (ref "U$19") (pin "B11") (pinfunction "B11_B11") (pintype "bidirectional"))
    )
    (net (code "75") (name "unconnected-(U$19-PadB12)") (class "Default")
      (node (ref "U$19") (pin "B12") (pinfunction "B12_B12") (pintype "bidirectional"))
    )
    (net (code "76") (name "unconnected-(U$19-PadB13)") (class "Default")
      (node (ref "U$19") (pin "B13") (pinfunction "B13_B13") (pintype "bidirectional"))
    )
    (net (code "77") (name "unconnected-(U$19-PadB15)") (class "Default")
      (node (ref "U$19") (pin "B15") (pinfunction "B15_B15") (pintype "bidirectional"))
    )
    (net (code "78") (name "unconnected-(U$19-PadB16)") (class "Default")
      (node (ref "U$19") (pin "B16") (pinfunction "B16_B16") (pintype "bidirectional"))
    )
    (net (code "79") (name "unconnected-(U$19-PadB17)") (class "Default")
      (node (ref "U$19") (pin "B17") (pinfunction "B17_B17") (pintype "bidirectional"))
    )
    (net (code "80") (name "unconnected-(U$19-PadB18)") (class "Default")
      (node (ref "U$19") (pin "B18") (pinfunction "B18_B18") (pintype "bidirectional"))
    )
    (net (code "81") (name "unconnected-(U$19-PadB19)") (class "Default")
      (node (ref "U$19") (pin "B19") (pinfunction "B19_B19") (pintype "bidirectional"))
    )
    (net (code "82") (name "unconnected-(U$19-PadB20)") (class "Default")
      (node (ref "U$19") (pin "B20") (pinfunction "B20_B20") (pintype "bidirectional"))
    )
    (net (code "83") (name "unconnected-(U$19-PadB21)") (class "Default")
      (node (ref "U$19") (pin "B21") (pinfunction "B21_B21") (pintype "bidirectional"))
    )
    (net (code "84") (name "unconnected-(U$19-PadB22)") (class "Default")
      (node (ref "U$19") (pin "B22") (pinfunction "B22_B22") (pintype "bidirectional"))
    )
    (net (code "85") (name "unconnected-(U$19-PadB23)") (class "Default")
      (node (ref "U$19") (pin "B23") (pinfunction "B23_B23") (pintype "bidirectional"))
    )
  )
)
